# AD9851_2.net
KiCad netlist of a schematic drawn in Altium Designer
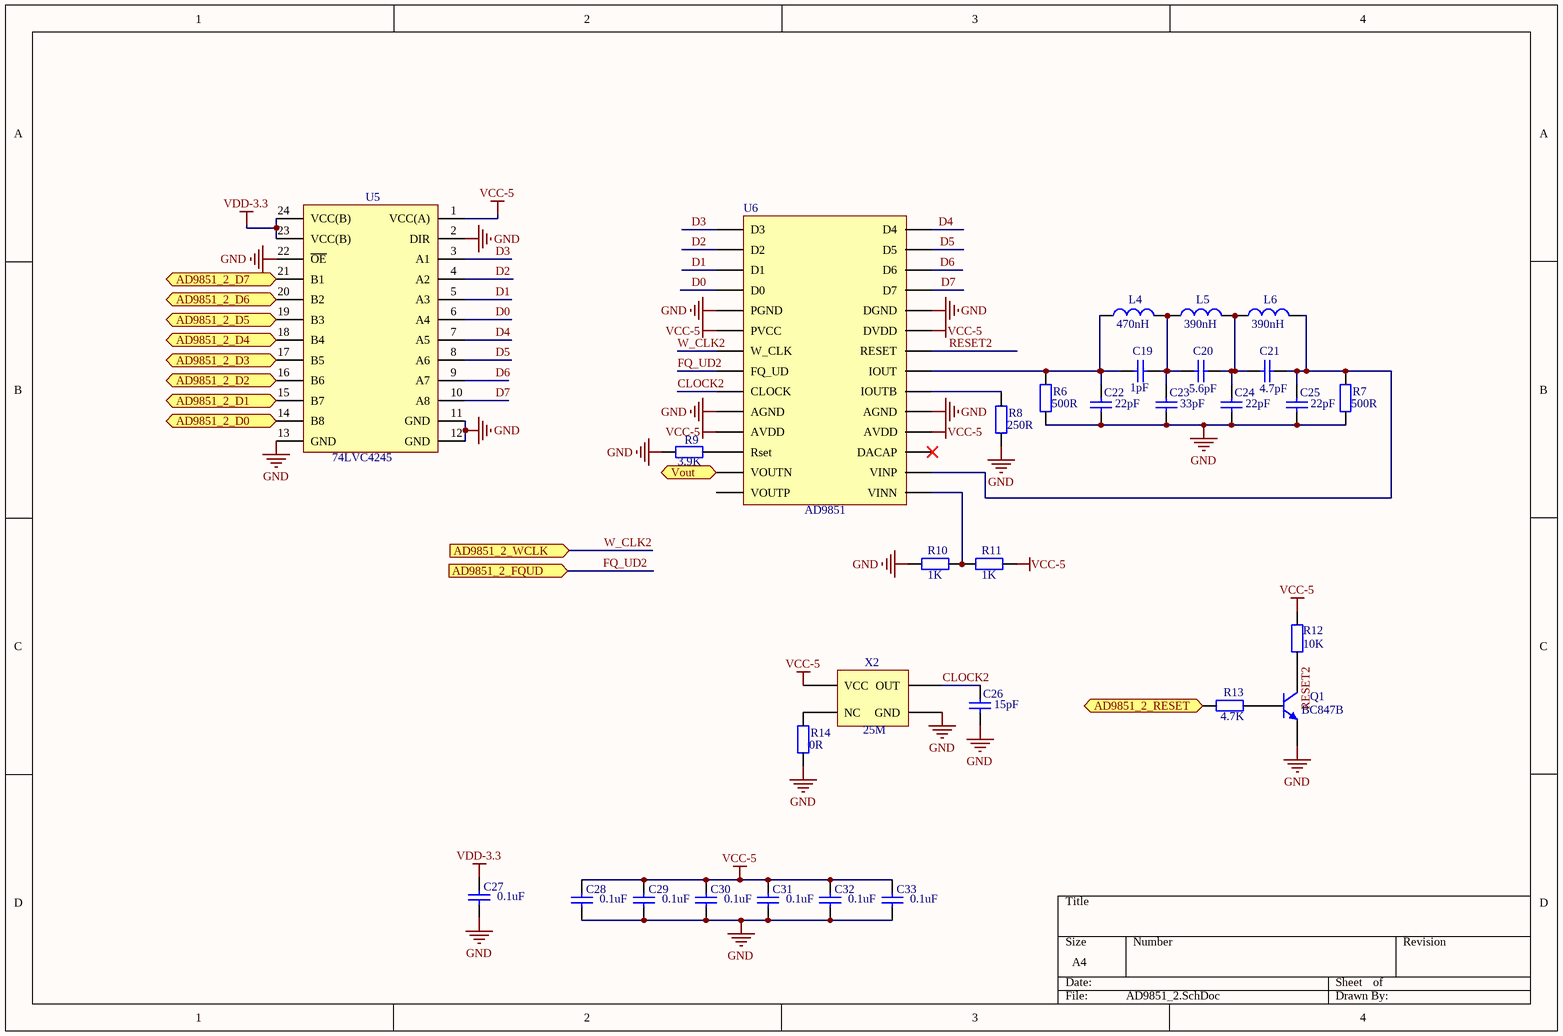
[diagram p0: AD9851_2.SchDoc]

(export (version "E")
  (design (tool "Eeschema 10.0.6"))
  (components
    (comp (ref "C19")
      (value "1pF")
      (footprint "0603")
      (fields (field (name "Comment") "Capacitor-0603"))
      (libsource (lib "原理图库") (part "Capacitor-0603"))
    )
    (comp (ref "C20")
      (value "5.6pF")
      (footprint "0603")
      (fields (field (name "Comment") "Capacitor-0603"))
      (libsource (lib "原理图库") (part "Capacitor-0603"))
    )
    (comp (ref "C21")
      (value "4.7pF")
      (footprint "0603")
      (fields (field (name "Comment") "Capacitor-0603"))
      (libsource (lib "原理图库") (part "Capacitor-0603"))
    )
    (comp (ref "C22")
      (value "22pF")
      (footprint "0603")
      (fields (field (name "Comment") "Capacitor-0603"))
      (libsource (lib "原理图库") (part "Capacitor-0603"))
    )
    (comp (ref "C23")
      (value "33pF")
      (footprint "0603")
      (fields (field (name "Comment") "Capacitor-0603"))
      (libsource (lib "原理图库") (part "Capacitor-0603"))
    )
    (comp (ref "C24")
      (value "22pF")
      (footprint "0603")
      (fields (field (name "Comment") "Capacitor-0603"))
      (libsource (lib "原理图库") (part "Capacitor-0603"))
    )
    (comp (ref "C25")
      (value "22pF")
      (footprint "0603")
      (fields (field (name "Comment") "Capacitor-0603"))
      (libsource (lib "原理图库") (part "Capacitor-0603"))
    )
    (comp (ref "C26")
      (value "15pF")
      (footprint "0603")
      (fields (field (name "Comment") "Capacitor-0603"))
      (libsource (lib "原理图库") (part "Capacitor-0603"))
    )
    (comp (ref "C27")
      (value "0.1uF")
      (footprint "0603")
      (fields (field (name "Comment") "Capacitor-0603"))
      (libsource (lib "原理图库") (part "Capacitor-0603"))
    )
    (comp (ref "C28")
      (value "0.1uF")
      (footprint "0603")
      (fields (field (name "Comment") "Capacitor-0603"))
      (libsource (lib "原理图库") (part "Capacitor-0603"))
    )
    (comp (ref "C29")
      (value "0.1uF")
      (footprint "0603")
      (fields (field (name "Comment") "Capacitor-0603"))
      (libsource (lib "原理图库") (part "Capacitor-0603"))
    )
    (comp (ref "C30")
      (value "0.1uF")
      (footprint "0603")
      (fields (field (name "Comment") "Capacitor-0603"))
      (libsource (lib "原理图库") (part "Capacitor-0603"))
    )
    (comp (ref "C31")
      (value "0.1uF")
      (footprint "0603")
      (fields (field (name "Comment") "Capacitor-0603"))
      (libsource (lib "原理图库") (part "Capacitor-0603"))
    )
    (comp (ref "C32")
      (value "0.1uF")
      (footprint "0603")
      (fields (field (name "Comment") "Capacitor-0603"))
      (libsource (lib "原理图库") (part "Capacitor-0603"))
    )
    (comp (ref "C33")
      (value "0.1uF")
      (footprint "0603")
      (fields (field (name "Comment") "Capacitor-0603"))
      (libsource (lib "原理图库") (part "Capacitor-0603"))
    )
    (comp (ref "L4")
      (value "470nH")
      (footprint "0805")
      (fields (field (name "Comment") "Inductor"))
      (libsource (lib "原理图库") (part "Inductor"))
    )
    (comp (ref "L5")
      (value "390nH")
      (footprint "0805")
      (fields (field (name "Comment") "Inductor"))
      (libsource (lib "原理图库") (part "Inductor"))
    )
    (comp (ref "L6")
      (value "390nH")
      (footprint "0805")
      (fields (field (name "Comment") "Inductor"))
      (libsource (lib "原理图库") (part "Inductor"))
    )
    (comp (ref "Q1")
      (value "BC847")
      (footprint "BC847B")
      (fields (field (name "NAME") "BC847B"))
      (libsource (lib "原理图库") (part "BC847"))
    )
    (comp (ref "R6")
      (value "500R")
      (footprint "0603")
      (fields (field (name "Comment") "Resistor-0603"))
      (libsource (lib "") (part "Resistor-0603_1"))
    )
    (comp (ref "R7")
      (value "500R")
      (footprint "0603")
      (fields (field (name "Comment") "Resistor-0603"))
      (libsource (lib "") (part "Resistor-0603_1"))
    )
    (comp (ref "R8")
      (value "250R")
      (footprint "0603")
      (fields (field (name "Comment") "Resistor-0603"))
      (libsource (lib "") (part "Resistor-0603_1"))
    )
    (comp (ref "R9")
      (value "3.9K")
      (footprint "0603")
      (fields (field (name "Comment") "Resistor-0603"))
      (libsource (lib "原理图库") (part "Resistor-0603"))
    )
    (comp (ref "R10")
      (value "1K")
      (footprint "0603")
      (fields (field (name "Comment") "Resistor-0603"))
      (libsource (lib "原理图库") (part "Resistor-0603"))
    )
    (comp (ref "R11")
      (value "1K")
      (footprint "0603")
      (fields (field (name "Comment") "Resistor-0603"))
      (libsource (lib "原理图库") (part "Resistor-0603"))
    )
    (comp (ref "R12")
      (value "10K")
      (footprint "0603")
      (fields (field (name "Comment") "Resistor-0603"))
      (libsource (lib "") (part "Resistor-0603_1"))
    )
    (comp (ref "R13")
      (value "4.7K")
      (footprint "0603")
      (fields (field (name "Comment") "Resistor-0603"))
      (libsource (lib "原理图库") (part "Resistor-0603"))
    )
    (comp (ref "R14")
      (value "0R")
      (footprint "0603")
      (fields (field (name "Comment") "Resistor-0603"))
      (libsource (lib "") (part "Resistor-0603_1"))
    )
    (comp (ref "U5")
      (value "74LVC4245")
      (footprint "74LVC4245-PW")
      (fields (field (name "NAME") "74LVC4245"))
      (libsource (lib "原理图库") (part "74LVC4245"))
    )
    (comp (ref "U6")
      (value "AD9851")
      (footprint "AD9851")
      (fields (field (name "NAME") "AD9851"))
      (libsource (lib "原理图库") (part "AD9851"))
    )
    (comp (ref "X2")
      (value "25M")
      (footprint "有源晶振7050")
      (fields (field (name "Comment") "有源晶振"))
      (libsource (lib "原理图库") (part "有源晶振"))
    )
  )
  (nets
    (net (code "1") (name "/AD9851_2_D0") (class "Default")
      (node (ref "U5") (pin "14") (pinfunction "B8_14") (pintype "passive"))
    )
    (net (code "2") (name "/AD9851_2_D1") (class "Default")
      (node (ref "U5") (pin "15") (pinfunction "B7_15") (pintype "passive"))
    )
    (net (code "3") (name "/AD9851_2_D2") (class "Default")
      (node (ref "U5") (pin "16") (pinfunction "B6_16") (pintype "passive"))
    )
    (net (code "4") (name "/AD9851_2_D3") (class "Default")
      (node (ref "U5") (pin "17") (pinfunction "B5_17") (pintype "passive"))
    )
    (net (code "5") (name "/AD9851_2_D4") (class "Default")
      (node (ref "U5") (pin "18") (pinfunction "B4_18") (pintype "passive"))
    )
    (net (code "6") (name "/AD9851_2_D5") (class "Default")
      (node (ref "U5") (pin "19") (pinfunction "B3_19") (pintype "passive"))
    )
    (net (code "7") (name "/AD9851_2_D6") (class "Default")
      (node (ref "U5") (pin "20") (pinfunction "B2_20") (pintype "passive"))
    )
    (net (code "8") (name "/AD9851_2_D7") (class "Default")
      (node (ref "U5") (pin "21") (pinfunction "B1_21") (pintype "passive"))
    )
    (net (code "9") (name "/AD9851_2_RESET") (class "Default")
      (node (ref "R13") (pin "2") (pinfunction "2_2") (pintype "passive"))
    )
    (net (code "10") (name "/CLOCK2") (class "Default")
      (node (ref "C26") (pin "2") (pinfunction "2_2") (pintype "passive"))
      (node (ref "U6") (pin "9") (pinfunction "CLOCK_9") (pintype "passive"))
      (node (ref "X2") (pin "3") (pinfunction "OUT_3") (pintype "passive"))
    )
    (net (code "11") (name "/D0") (class "Default")
      (node (ref "U5") (pin "6") (pinfunction "A4_6") (pintype "passive"))
      (node (ref "U6") (pin "4") (pinfunction "D0_4") (pintype "passive"))
    )
    (net (code "12") (name "/D1") (class "Default")
      (node (ref "U5") (pin "5") (pinfunction "A3_5") (pintype "passive"))
      (node (ref "U6") (pin "3") (pinfunction "D1_3") (pintype "passive"))
    )
    (net (code "13") (name "/D2") (class "Default")
      (node (ref "U5") (pin "4") (pinfunction "A2_4") (pintype "passive"))
      (node (ref "U6") (pin "2") (pinfunction "D2_2") (pintype "passive"))
    )
    (net (code "14") (name "/D3") (class "Default")
      (node (ref "U5") (pin "3") (pinfunction "A1_3") (pintype "passive"))
      (node (ref "U6") (pin "1") (pinfunction "D3_1") (pintype "passive"))
    )
    (net (code "15") (name "/D4") (class "Default")
      (node (ref "U5") (pin "7") (pinfunction "A5_7") (pintype "passive"))
      (node (ref "U6") (pin "28") (pinfunction "D4_28") (pintype "passive"))
    )
    (net (code "16") (name "/D5") (class "Default")
      (node (ref "U5") (pin "8") (pinfunction "A6_8") (pintype "passive"))
      (node (ref "U6") (pin "27") (pinfunction "D5_27") (pintype "passive"))
    )
    (net (code "17") (name "/D6") (class "Default")
      (node (ref "U5") (pin "9") (pinfunction "A7_9") (pintype "passive"))
      (node (ref "U6") (pin "26") (pinfunction "D6_26") (pintype "passive"))
    )
    (net (code "18") (name "/D7") (class "Default")
      (node (ref "U5") (pin "10") (pinfunction "A8_10") (pintype "passive"))
      (node (ref "U6") (pin "25") (pinfunction "D7_25") (pintype "passive"))
    )
    (net (code "19") (name "/FQ_UD2") (class "Default")
      (node (ref "U6") (pin "8") (pinfunction "FQ_UD_8") (pintype "passive"))
    )
    (net (code "20") (name "/RESET2") (class "Default")
      (node (ref "Q1") (pin "3") (pinfunction "C_3") (pintype "passive"))
      (node (ref "R12") (pin "1") (pinfunction "1_1") (pintype "passive"))
      (node (ref "U6") (pin "22") (pinfunction "RESET_22") (pintype "passive"))
    )
    (net (code "21") (name "/Vout") (class "Default")
      (node (ref "U6") (pin "13") (pinfunction "VOUTN_13") (pintype "passive"))
    )
    (net (code "22") (name "/W_CLK2") (class "Default")
      (node (ref "U6") (pin "7") (pinfunction "W_CLK_7") (pintype "passive"))
    )
    (net (code "23") (name "GND") (class "Default")
      (node (ref "C22") (pin "1") (pinfunction "1_1") (pintype "passive"))
      (node (ref "C23") (pin "1") (pinfunction "1_1") (pintype "passive"))
      (node (ref "C24") (pin "1") (pinfunction "1_1") (pintype "passive"))
      (node (ref "C25") (pin "1") (pinfunction "1_1") (pintype "passive"))
      (node (ref "C26") (pin "1") (pinfunction "1_1") (pintype "passive"))
      (node (ref "C27") (pin "2") (pinfunction "2_2") (pintype "passive"))
      (node (ref "C28") (pin "2") (pinfunction "2_2") (pintype "passive"))
      (node (ref "C29") (pin "2") (pinfunction "2_2") (pintype "passive"))
      (node (ref "C30") (pin "2") (pinfunction "2_2") (pintype "passive"))
      (node (ref "C31") (pin "2") (pinfunction "2_2") (pintype "passive"))
      (node (ref "C32") (pin "2") (pinfunction "2_2") (pintype "passive"))
      (node (ref "C33") (pin "2") (pinfunction "2_2") (pintype "passive"))
      (node (ref "Q1") (pin "1") (pinfunction "E_1") (pintype "passive"))
      (node (ref "R10") (pin "2") (pinfunction "2_2") (pintype "passive"))
      (node (ref "R14") (pin "1") (pinfunction "1_1") (pintype "passive"))
      (node (ref "R6") (pin "1") (pinfunction "1_1") (pintype "passive"))
      (node (ref "R7") (pin "1") (pinfunction "1_1") (pintype "passive"))
      (node (ref "R8") (pin "1") (pinfunction "1_1") (pintype "passive"))
      (node (ref "R9") (pin "2") (pinfunction "2_2") (pintype "passive"))
      (node (ref "U5") (pin "11") (pinfunction "GND_11") (pintype "passive"))
      (node (ref "U5") (pin "12") (pinfunction "GND_12") (pintype "passive"))
      (node (ref "U5") (pin "13") (pinfunction "GND_13") (pintype "passive"))
      (node (ref "U5") (pin "2") (pinfunction "DIR_2") (pintype "passive"))
      (node (ref "U5") (pin "22") (pinfunction "~{OE}_22") (pintype "passive"))
      (node (ref "U6") (pin "10") (pinfunction "AGND_10") (pintype "passive"))
      (node (ref "U6") (pin "19") (pinfunction "AGND_19") (pintype "passive"))
      (node (ref "U6") (pin "24") (pinfunction "DGND_24") (pintype "passive"))
      (node (ref "U6") (pin "5") (pinfunction "PGND_5") (pintype "passive"))
      (node (ref "X2") (pin "2") (pinfunction "GND_2") (pintype "passive"))
    )
    (net (code "24") (name "Net-(C19-Pad1)") (class "Default")
      (node (ref "C19") (pin "1") (pinfunction "1_1") (pintype "passive"))
      (node (ref "C20") (pin "2") (pinfunction "2_2") (pintype "passive"))
      (node (ref "C23") (pin "2") (pinfunction "2_2") (pintype "passive"))
      (node (ref "L4") (pin "2") (pinfunction "2_2") (pintype "passive"))
      (node (ref "L5") (pin "1") (pinfunction "1_1") (pintype "passive"))
    )
    (net (code "25") (name "Net-(C20-Pad1)") (class "Default")
      (node (ref "C20") (pin "1") (pinfunction "1_1") (pintype "passive"))
      (node (ref "C21") (pin "2") (pinfunction "2_2") (pintype "passive"))
      (node (ref "C24") (pin "2") (pinfunction "2_2") (pintype "passive"))
      (node (ref "L5") (pin "2") (pinfunction "2_2") (pintype "passive"))
      (node (ref "L6") (pin "1") (pinfunction "1_1") (pintype "passive"))
    )
    (net (code "26") (name "Net-(Q1-B)") (class "Default")
      (node (ref "Q1") (pin "2") (pinfunction "B_2") (pintype "passive"))
      (node (ref "R13") (pin "1") (pinfunction "1_1") (pintype "passive"))
    )
    (net (code "27") (name "Net-(U6-IOUT)") (class "Default")
      (node (ref "C19") (pin "2") (pinfunction "2_2") (pintype "passive"))
      (node (ref "C22") (pin "2") (pinfunction "2_2") (pintype "passive"))
      (node (ref "L4") (pin "1") (pinfunction "1_1") (pintype "passive"))
      (node (ref "R6") (pin "2") (pinfunction "2_2") (pintype "passive"))
      (node (ref "U6") (pin "21") (pinfunction "IOUT_21") (pintype "passive"))
    )
    (net (code "28") (name "Net-(U6-IOUTB)") (class "Default")
      (node (ref "R8") (pin "2") (pinfunction "2_2") (pintype "passive"))
      (node (ref "U6") (pin "20") (pinfunction "IOUTB_20") (pintype "passive"))
    )
    (net (code "29") (name "Net-(U6-Rset)") (class "Default")
      (node (ref "R9") (pin "1") (pinfunction "1_1") (pintype "passive"))
      (node (ref "U6") (pin "12") (pinfunction "Rset_12") (pintype "passive"))
    )
    (net (code "30") (name "Net-(U6-VINN)") (class "Default")
      (node (ref "R10") (pin "1") (pinfunction "1_1") (pintype "passive"))
      (node (ref "R11") (pin "2") (pinfunction "2_2") (pintype "passive"))
      (node (ref "U6") (pin "15") (pinfunction "VINN_15") (pintype "passive"))
    )
    (net (code "31") (name "Net-(U6-VINP)") (class "Default")
      (node (ref "C21") (pin "1") (pinfunction "1_1") (pintype "passive"))
      (node (ref "C25") (pin "2") (pinfunction "2_2") (pintype "passive"))
      (node (ref "L6") (pin "2") (pinfunction "2_2") (pintype "passive"))
      (node (ref "R7") (pin "2") (pinfunction "2_2") (pintype "passive"))
      (node (ref "U6") (pin "16") (pinfunction "VINP_16") (pintype "passive"))
    )
    (net (code "32") (name "Net-(X2-NC)") (class "Default")
      (node (ref "R14") (pin "2") (pinfunction "2_2") (pintype "passive"))
      (node (ref "X2") (pin "1") (pinfunction "NC_1") (pintype "passive"))
    )
    (net (code "33") (name "VCC-5") (class "Default")
      (node (ref "C28") (pin "1") (pinfunction "1_1") (pintype "passive"))
      (node (ref "C29") (pin "1") (pinfunction "1_1") (pintype "passive"))
      (node (ref "C30") (pin "1") (pinfunction "1_1") (pintype "passive"))
      (node (ref "C31") (pin "1") (pinfunction "1_1") (pintype "passive"))
      (node (ref "C32") (pin "1") (pinfunction "1_1") (pintype "passive"))
      (node (ref "C33") (pin "1") (pinfunction "1_1") (pintype "passive"))
      (node (ref "R11") (pin "1") (pinfunction "1_1") (pintype "passive"))
      (node (ref "R12") (pin "2") (pinfunction "2_2") (pintype "passive"))
      (node (ref "U5") (pin "1") (pinfunction "VCC(A)_1") (pintype "passive"))
      (node (ref "U6") (pin "11") (pinfunction "AVDD_11") (pintype "passive"))
      (node (ref "U6") (pin "18") (pinfunction "AVDD_18") (pintype "passive"))
      (node (ref "U6") (pin "23") (pinfunction "DVDD_23") (pintype "passive"))
      (node (ref "U6") (pin "6") (pinfunction "PVCC_6") (pintype "passive"))
      (node (ref "X2") (pin "4") (pinfunction "VCC_4") (pintype "passive"))
    )
    (net (code "34") (name "VDD-3.3") (class "Default")
      (node (ref "C27") (pin "1") (pinfunction "1_1") (pintype "passive"))
      (node (ref "U5") (pin "23") (pinfunction "VCC(B)_23") (pintype "passive"))
      (node (ref "U5") (pin "24") (pinfunction "VCC(B)_24") (pintype "passive"))
    )
    (net (code "35") (name "unconnected-(U6-DACAP-Pad17)") (class "Default")
      (node (ref "U6") (pin "17") (pinfunction "DACAP_17") (pintype "passive+no_connect"))
    )
    (net (code "36") (name "unconnected-(U6-VOUTP-Pad14)") (class "Default")
      (node (ref "U6") (pin "14") (pinfunction "VOUTP_14") (pintype "passive"))
    )
  )
)
